# UART_Multiplexor.net
KiCad netlist of a schematic drawn in Altium Designer
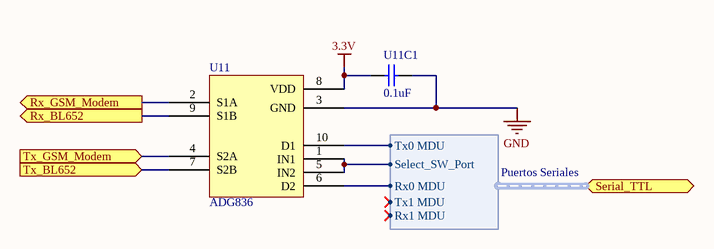
[diagram p0: UART_Multiplexor.SchDoc]

(export (version "E")
  (design (tool "Eeschema 10.0.6"))
  (components
    (comp (ref "U11")
      (value "ADG836")
      (footprint "ADG836")
      (description "IC SWITCH DUAL SPDT 10MSOP")
      (fields
        (field (name "MANUFACTURER") "Analog Devices Inc.")
        (field (name "MANUFACTURER PART NUMBER") "ADG836YRMZ")
      )
      (libsource (lib "ADG836") (part "ADG836"))
    )
    (comp (ref "U11C1")
      (value "0.1uF")
      (footprint "0603 - CAP")
      (description "CAP CERAMIC 0.1UF, 25V, X7R, 0603")
      (fields
        (field (name "MANUFACTURER PART NUMBER") "CGJ3E2X7R1E104K080AA")
        (field (name "MANUFACTURER") "TDK Corporation")
      )
      (libsource (lib "*") (part "Cap"))
    )
  )
  (nets
    (net (code "3") (name "/Rx0 MDU") (class "Default")
      (node (ref "U11") (pin "6") (pinfunction "D2_6") (pintype "passive"))
    )
    (net (code "4") (name "/Rx_BL652") (class "Default")
      (node (ref "U11") (pin "9") (pinfunction "S1B_9") (pintype "passive"))
    )
    (net (code "5") (name "/Rx_GSM_Modem") (class "Default")
      (node (ref "U11") (pin "2") (pinfunction "S1A_2") (pintype "passive"))
    )
    (net (code "6") (name "/Select_SW_Port") (class "Default")
      (node (ref "U11") (pin "1") (pinfunction "IN1_1") (pintype "passive"))
      (node (ref "U11") (pin "5") (pinfunction "IN2_5") (pintype "passive"))
    )
    (net (code "7") (name "/Tx0 MDU") (class "Default")
      (node (ref "U11") (pin "10") (pinfunction "D1_10") (pintype "passive"))
    )
    (net (code "8") (name "/Tx_BL652") (class "Default")
      (node (ref "U11") (pin "7") (pinfunction "S2B_7") (pintype "passive"))
    )
    (net (code "9") (name "/Tx_GSM_Modem") (class "Default")
      (node (ref "U11") (pin "4") (pinfunction "S2A_4") (pintype "passive"))
    )
    (net (code "11") (name "3.3V") (class "Default")
      (node (ref "U11") (pin "8") (pinfunction "VDD_8") (pintype "passive"))
      (node (ref "U11C1") (pin "2") (pinfunction "2_2") (pintype "passive"))
    )
    (net (code "12") (name "GND") (class "Default")
      (node (ref "U11") (pin "3") (pinfunction "GND_3") (pintype "passive"))
      (node (ref "U11C1") (pin "1") (pinfunction "1_1") (pintype "passive"))
    )
  )
)
